# AvrispArduino.net
KiCad netlist of a schematic drawn in EAGLE
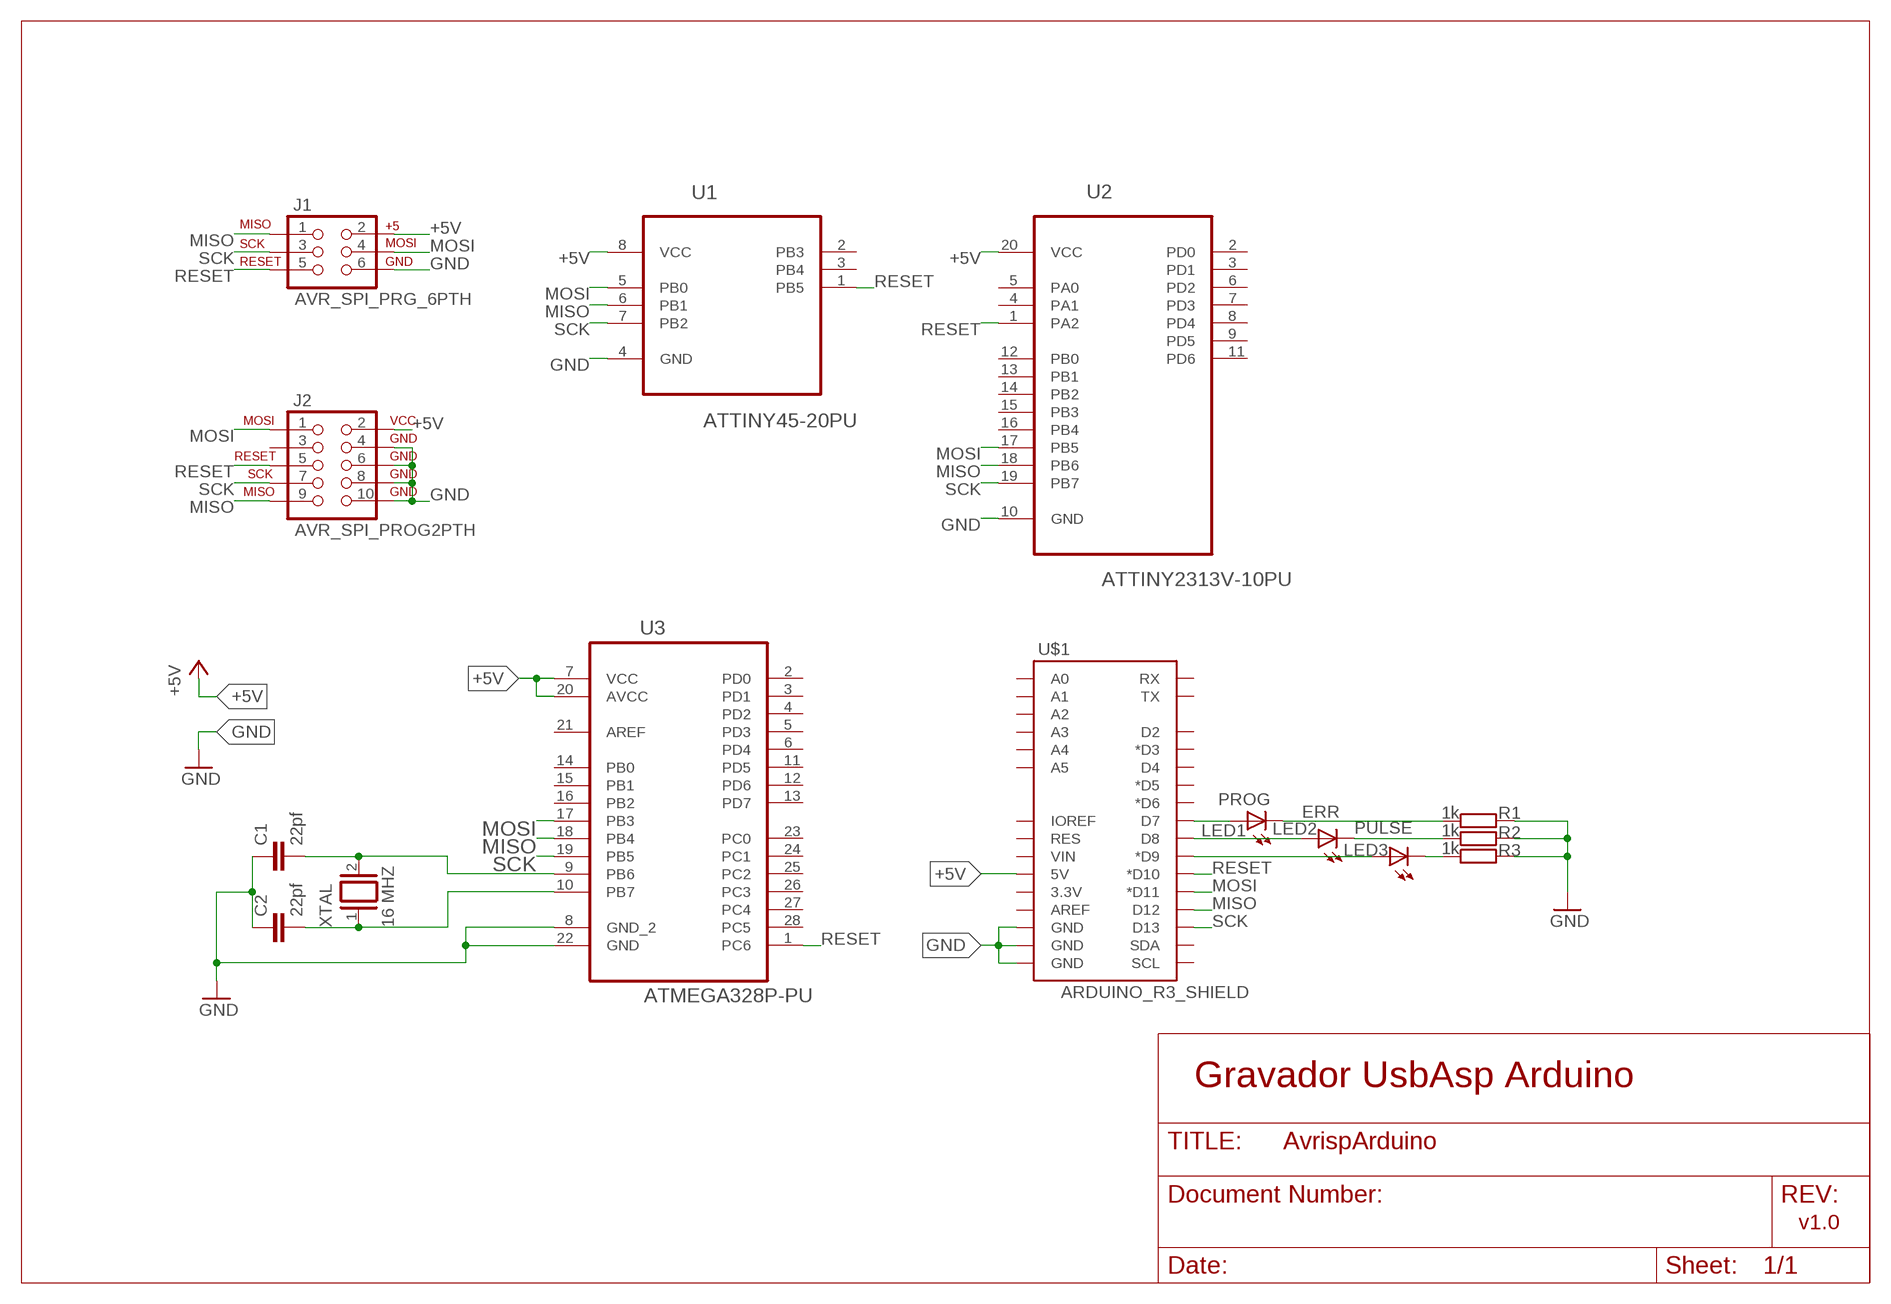
[diagram p0: schematic, sheet 1]

(export (version "E")
  (design (tool "Eeschema 10.0.6"))
  (components
    (comp (ref "C1")
      (value "22pf")
      (footprint "eagle-import:C025-025X050")
      (libsource (lib "eagle-import") (part "C-EU025-025X050"))
    )
    (comp (ref "C2")
      (value "22pf")
      (footprint "eagle-import:C025-025X050")
      (libsource (lib "eagle-import") (part "C-EU025-025X050"))
    )
    (comp (ref "J1")
      (value "AVR_SPI_PRG_6PTH")
      (footprint "eagle-import:2X3")
      (libsource (lib "eagle-import") (part "AVR_SPI_PRG_6PTH"))
    )
    (comp (ref "J2")
      (value "AVR_SPI_PROG2PTH")
      (footprint "eagle-import:AVR_ICSP")
      (libsource (lib "eagle-import") (part "AVR_SPI_PROG2PTH"))
    )
    (comp (ref "LED1")
      (value "PROG")
      (footprint "eagle-import:LED3MM")
      (libsource (lib "eagle-import") (part "LED3MM"))
    )
    (comp (ref "LED2")
      (value "ERR")
      (footprint "eagle-import:LED3MM")
      (libsource (lib "eagle-import") (part "LED3MM"))
    )
    (comp (ref "LED3")
      (value "PULSE")
      (footprint "eagle-import:LED3MM")
      (libsource (lib "eagle-import") (part "LED3MM"))
    )
    (comp (ref "R1")
      (value "1k")
      (footprint "eagle-import:0207_10")
      (libsource (lib "eagle-import") (part "R-EU_0207/10"))
    )
    (comp (ref "R2")
      (value "1k")
      (footprint "eagle-import:0207_10")
      (libsource (lib "eagle-import") (part "R-EU_0207/10"))
    )
    (comp (ref "R3")
      (value "1k")
      (footprint "eagle-import:0207_10")
      (libsource (lib "eagle-import") (part "R-EU_0207/10"))
    )
    (comp (ref "U$1")
      (value "ARDUINO_R3_SHIELD")
      (footprint "eagle-import:UNO_R3_SHIELD")
      (libsource (lib "eagle-import") (part "ARDUINO_R3_SHIELD"))
    )
    (comp (ref "U1")
      (value "ATTINY45-20PU")
      (footprint "eagle-import:DIP254P762X533-8")
      (libsource (lib "eagle-import") (part "ATTINY45-20PU"))
    )
    (comp (ref "U2")
      (value "ATTINY2313V-10PU")
      (footprint "eagle-import:DIP254P762X533-20")
      (libsource (lib "eagle-import") (part "ATTINY2313V-10PU"))
    )
    (comp (ref "U3")
      (value "ATMEGA328P-PU")
      (footprint "eagle-import:DIP254P762X457-28")
      (libsource (lib "eagle-import") (part "ATMEGA328P-PU"))
    )
    (comp (ref "XTAL")
      (value "16 MHZ")
      (footprint "eagle-import:QS")
      (libsource (lib "eagle-import") (part "XTAL/S"))
    )
  )
  (nets
    (net (code "1") (name "+5V") (class "Default")
      (node (ref "J1") (pin "2") (pinfunction "2_2") (pintype "passive"))
      (node (ref "J2") (pin "2") (pinfunction "VCC_2") (pintype "power_in"))
      (node (ref "U$1") (pin "5V") (pinfunction "5V_5V") (pintype "bidirectional"))
      (node (ref "U1") (pin "8") (pinfunction "VCC_8") (pintype "power_in"))
      (node (ref "U2") (pin "20") (pinfunction "VCC_20") (pintype "power_in"))
      (node (ref "U3") (pin "20") (pinfunction "AVCC_20") (pintype "power_in"))
      (node (ref "U3") (pin "7") (pinfunction "VCC_7") (pintype "power_in"))
    )
    (net (code "2") (name "/MISO") (class "Default")
      (node (ref "J1") (pin "1") (pinfunction "1_1") (pintype "passive"))
      (node (ref "J2") (pin "9") (pinfunction "MISO_9") (pintype "passive"))
      (node (ref "U$1") (pin "D12") (pinfunction "D12_D12") (pintype "bidirectional"))
      (node (ref "U1") (pin "6") (pinfunction "PB1_6") (pintype "bidirectional"))
      (node (ref "U2") (pin "18") (pinfunction "PB6_18") (pintype "bidirectional"))
      (node (ref "U3") (pin "18") (pinfunction "PB4_18") (pintype "bidirectional"))
    )
    (net (code "3") (name "/MOSI") (class "Default")
      (node (ref "J1") (pin "4") (pinfunction "4_4") (pintype "passive"))
      (node (ref "J2") (pin "1") (pinfunction "MOSI_1") (pintype "passive"))
      (node (ref "U$1") (pin "D11") (pinfunction "*D11_D11") (pintype "bidirectional"))
      (node (ref "U1") (pin "5") (pinfunction "PB0_5") (pintype "bidirectional"))
      (node (ref "U2") (pin "17") (pinfunction "PB5_17") (pintype "bidirectional"))
      (node (ref "U3") (pin "17") (pinfunction "PB3_17") (pintype "bidirectional"))
    )
    (net (code "4") (name "/RESET") (class "Default")
      (node (ref "J1") (pin "5") (pinfunction "5_5") (pintype "passive"))
      (node (ref "J2") (pin "5") (pinfunction "RESET_5") (pintype "passive"))
      (node (ref "U$1") (pin "D10") (pinfunction "*D10_D10") (pintype "bidirectional"))
      (node (ref "U1") (pin "1") (pinfunction "PB5_1") (pintype "bidirectional"))
      (node (ref "U2") (pin "1") (pinfunction "PA2_1") (pintype "bidirectional"))
      (node (ref "U3") (pin "1") (pinfunction "PC6_1") (pintype "bidirectional"))
    )
    (net (code "5") (name "/SCK") (class "Default")
      (node (ref "J1") (pin "3") (pinfunction "3_3") (pintype "passive"))
      (node (ref "J2") (pin "7") (pinfunction "SCK_7") (pintype "passive"))
      (node (ref "U$1") (pin "D13") (pinfunction "D13_D13") (pintype "bidirectional"))
      (node (ref "U1") (pin "7") (pinfunction "PB2_7") (pintype "bidirectional"))
      (node (ref "U2") (pin "19") (pinfunction "PB7_19") (pintype "bidirectional"))
      (node (ref "U3") (pin "19") (pinfunction "PB5_19") (pintype "bidirectional"))
    )
    (net (code "6") (name "GND") (class "Default")
      (node (ref "C1") (pin "1") (pinfunction "1_1") (pintype "passive"))
      (node (ref "C2") (pin "1") (pinfunction "1_1") (pintype "passive"))
      (node (ref "J1") (pin "6") (pinfunction "6_6") (pintype "passive"))
      (node (ref "J2") (pin "10") (pinfunction "GND_10") (pintype "power_in"))
      (node (ref "J2") (pin "4") (pinfunction "GND_4") (pintype "power_in"))
      (node (ref "J2") (pin "6") (pinfunction "GND_6") (pintype "power_in"))
      (node (ref "J2") (pin "8") (pinfunction "GND_8") (pintype "power_in"))
      (node (ref "R1") (pin "2") (pinfunction "2_2") (pintype "passive"))
      (node (ref "R2") (pin "2") (pinfunction "2_2") (pintype "passive"))
      (node (ref "R3") (pin "2") (pinfunction "2_2") (pintype "passive"))
      (node (ref "U$1") (pin "GND@0") (pinfunction "GND_GND@0") (pintype "bidirectional"))
      (node (ref "U$1") (pin "GND@1") (pinfunction "GND_GND@1") (pintype "bidirectional"))
      (node (ref "U$1") (pin "GND@2") (pinfunction "GND_GND@2") (pintype "bidirectional"))
      (node (ref "U1") (pin "4") (pinfunction "GND_4") (pintype "passive"))
      (node (ref "U2") (pin "10") (pinfunction "GND_10") (pintype "passive"))
      (node (ref "U3") (pin "22") (pinfunction "GND_22") (pintype "passive"))
      (node (ref "U3") (pin "8") (pinfunction "GND_2_8") (pintype "passive"))
    )
    (net (code "7") (name "Net-(LED1-C)") (class "Default")
      (node (ref "LED1") (pin "K") (pinfunction "C_K") (pintype "passive"))
      (node (ref "R1") (pin "1") (pinfunction "1_1") (pintype "passive"))
    )
    (net (code "8") (name "Net-(LED1-PadA)") (class "Default")
      (node (ref "LED1") (pin "A") (pinfunction "A_A") (pintype "passive"))
      (node (ref "U$1") (pin "D7") (pinfunction "D7_D7") (pintype "bidirectional"))
    )
    (net (code "9") (name "Net-(LED2-C)") (class "Default")
      (node (ref "LED2") (pin "K") (pinfunction "C_K") (pintype "passive"))
      (node (ref "R2") (pin "1") (pinfunction "1_1") (pintype "passive"))
    )
    (net (code "10") (name "Net-(LED2-PadA)") (class "Default")
      (node (ref "LED2") (pin "A") (pinfunction "A_A") (pintype "passive"))
      (node (ref "U$1") (pin "D8") (pinfunction "D8_D8") (pintype "bidirectional"))
    )
    (net (code "11") (name "Net-(LED3-C)") (class "Default")
      (node (ref "LED3") (pin "K") (pinfunction "C_K") (pintype "passive"))
      (node (ref "R3") (pin "1") (pinfunction "1_1") (pintype "passive"))
    )
    (net (code "12") (name "Net-(U$1-*D9)") (class "Default")
      (node (ref "LED3") (pin "A") (pinfunction "A_A") (pintype "passive"))
      (node (ref "U$1") (pin "D9") (pinfunction "*D9_D9") (pintype "bidirectional"))
    )
    (net (code "13") (name "Net-(U3-PB6)") (class "Default")
      (node (ref "C1") (pin "2") (pinfunction "2_2") (pintype "passive"))
      (node (ref "U3") (pin "9") (pinfunction "PB6_9") (pintype "bidirectional"))
      (node (ref "XTAL") (pin "2") (pinfunction "2_2") (pintype "passive"))
    )
    (net (code "14") (name "Net-(U3-PB7)") (class "Default")
      (node (ref "C2") (pin "2") (pinfunction "2_2") (pintype "passive"))
      (node (ref "U3") (pin "10") (pinfunction "PB7_10") (pintype "bidirectional"))
      (node (ref "XTAL") (pin "1") (pinfunction "1_1") (pintype "passive"))
    )
    (net (code "15") (name "unconnected-(J2-NC-Pad3)") (class "Default")
      (node (ref "J2") (pin "3") (pinfunction "NC_3") (pintype "no_connect"))
    )
    (net (code "16") (name "unconnected-(U$1-*D3-PadD3)") (class "Default")
      (node (ref "U$1") (pin "D3") (pinfunction "*D3_D3") (pintype "bidirectional"))
    )
    (net (code "17") (name "unconnected-(U$1-*D5-PadD5)") (class "Default")
      (node (ref "U$1") (pin "D5") (pinfunction "*D5_D5") (pintype "bidirectional"))
    )
    (net (code "18") (name "unconnected-(U$1-*D6-PadD6)") (class "Default")
      (node (ref "U$1") (pin "D6") (pinfunction "*D6_D6") (pintype "bidirectional"))
    )
    (net (code "19") (name "unconnected-(U$1-Pad3.3V)") (class "Default")
      (node (ref "U$1") (pin "3.3V") (pinfunction "3.3V_3.3V") (pintype "bidirectional"))
    )
    (net (code "20") (name "unconnected-(U$1-PadA0)") (class "Default")
      (node (ref "U$1") (pin "A0") (pinfunction "A0_A0") (pintype "bidirectional"))
    )
    (net (code "21") (name "unconnected-(U$1-PadA1)") (class "Default")
      (node (ref "U$1") (pin "A1") (pinfunction "A1_A1") (pintype "bidirectional"))
    )
    (net (code "22") (name "unconnected-(U$1-PadA2)") (class "Default")
      (node (ref "U$1") (pin "A2") (pinfunction "A2_A2") (pintype "bidirectional"))
    )
    (net (code "23") (name "unconnected-(U$1-PadA3)") (class "Default")
      (node (ref "U$1") (pin "A3") (pinfunction "A3_A3") (pintype "bidirectional"))
    )
    (net (code "24") (name "unconnected-(U$1-PadA4)") (class "Default")
      (node (ref "U$1") (pin "A4") (pinfunction "A4_A4") (pintype "bidirectional"))
    )
    (net (code "25") (name "unconnected-(U$1-PadA5)") (class "Default")
      (node (ref "U$1") (pin "A5") (pinfunction "A5_A5") (pintype "bidirectional"))
    )
    (net (code "26") (name "unconnected-(U$1-PadAREF)") (class "Default")
      (node (ref "U$1") (pin "AREF") (pinfunction "AREF_AREF") (pintype "bidirectional"))
    )
    (net (code "27") (name "unconnected-(U$1-PadD2)") (class "Default")
      (node (ref "U$1") (pin "D2") (pinfunction "D2_D2") (pintype "bidirectional"))
    )
    (net (code "28") (name "unconnected-(U$1-PadD4)") (class "Default")
      (node (ref "U$1") (pin "D4") (pinfunction "D4_D4") (pintype "bidirectional"))
    )
    (net (code "29") (name "unconnected-(U$1-PadIOREF)") (class "Default")
      (node (ref "U$1") (pin "IOREF") (pinfunction "IOREF_IOREF") (pintype "bidirectional"))
    )
    (net (code "30") (name "unconnected-(U$1-PadRES)") (class "Default")
      (node (ref "U$1") (pin "RES") (pinfunction "RES_RES") (pintype "bidirectional"))
    )
    (net (code "31") (name "unconnected-(U$1-PadRX)") (class "Default")
      (node (ref "U$1") (pin "RX") (pinfunction "RX_RX") (pintype "bidirectional"))
    )
    (net (code "32") (name "unconnected-(U$1-PadSCL)") (class "Default")
      (node (ref "U$1") (pin "SCL") (pinfunction "SCL_SCL") (pintype "bidirectional"))
    )
    (net (code "33") (name "unconnected-(U$1-PadSDA)") (class "Default")
      (node (ref "U$1") (pin "SDA") (pinfunction "SDA_SDA") (pintype "bidirectional"))
    )
    (net (code "34") (name "unconnected-(U$1-PadTX)") (class "Default")
      (node (ref "U$1") (pin "TX") (pinfunction "TX_TX") (pintype "bidirectional"))
    )
    (net (code "35") (name "unconnected-(U$1-PadVIN)") (class "Default")
      (node (ref "U$1") (pin "VIN") (pinfunction "VIN_VIN") (pintype "bidirectional"))
    )
    (net (code "36") (name "unconnected-(U1-PB3-Pad2)") (class "Default")
      (node (ref "U1") (pin "2") (pinfunction "PB3_2") (pintype "bidirectional"))
    )
    (net (code "37") (name "unconnected-(U1-PB4-Pad3)") (class "Default")
      (node (ref "U1") (pin "3") (pinfunction "PB4_3") (pintype "bidirectional"))
    )
    (net (code "38") (name "unconnected-(U2-PA0-Pad5)") (class "Default")
      (node (ref "U2") (pin "5") (pinfunction "PA0_5") (pintype "bidirectional"))
    )
    (net (code "39") (name "unconnected-(U2-PA1-Pad4)") (class "Default")
      (node (ref "U2") (pin "4") (pinfunction "PA1_4") (pintype "bidirectional"))
    )
    (net (code "40") (name "unconnected-(U2-PB0-Pad12)") (class "Default")
      (node (ref "U2") (pin "12") (pinfunction "PB0_12") (pintype "bidirectional"))
    )
    (net (code "41") (name "unconnected-(U2-PB1-Pad13)") (class "Default")
      (node (ref "U2") (pin "13") (pinfunction "PB1_13") (pintype "bidirectional"))
    )
    (net (code "42") (name "unconnected-(U2-PB2-Pad14)") (class "Default")
      (node (ref "U2") (pin "14") (pinfunction "PB2_14") (pintype "bidirectional"))
    )
    (net (code "43") (name "unconnected-(U2-PB3-Pad15)") (class "Default")
      (node (ref "U2") (pin "15") (pinfunction "PB3_15") (pintype "bidirectional"))
    )
    (net (code "44") (name "unconnected-(U2-PB4-Pad16)") (class "Default")
      (node (ref "U2") (pin "16") (pinfunction "PB4_16") (pintype "bidirectional"))
    )
    (net (code "45") (name "unconnected-(U2-PD0-Pad2)") (class "Default")
      (node (ref "U2") (pin "2") (pinfunction "PD0_2") (pintype "bidirectional"))
    )
    (net (code "46") (name "unconnected-(U2-PD1-Pad3)") (class "Default")
      (node (ref "U2") (pin "3") (pinfunction "PD1_3") (pintype "bidirectional"))
    )
    (net (code "47") (name "unconnected-(U2-PD2-Pad6)") (class "Default")
      (node (ref "U2") (pin "6") (pinfunction "PD2_6") (pintype "bidirectional"))
    )
    (net (code "48") (name "unconnected-(U2-PD3-Pad7)") (class "Default")
      (node (ref "U2") (pin "7") (pinfunction "PD3_7") (pintype "bidirectional"))
    )
    (net (code "49") (name "unconnected-(U2-PD4-Pad8)") (class "Default")
      (node (ref "U2") (pin "8") (pinfunction "PD4_8") (pintype "bidirectional"))
    )
    (net (code "50") (name "unconnected-(U2-PD5-Pad9)") (class "Default")
      (node (ref "U2") (pin "9") (pinfunction "PD5_9") (pintype "bidirectional"))
    )
    (net (code "51") (name "unconnected-(U2-PD6-Pad11)") (class "Default")
      (node (ref "U2") (pin "11") (pinfunction "PD6_11") (pintype "bidirectional"))
    )
    (net (code "52") (name "unconnected-(U3-AREF-Pad21)") (class "Default")
      (node (ref "U3") (pin "21") (pinfunction "AREF_21") (pintype "input"))
    )
    (net (code "53") (name "unconnected-(U3-PB0-Pad14)") (class "Default")
      (node (ref "U3") (pin "14") (pinfunction "PB0_14") (pintype "bidirectional"))
    )
    (net (code "54") (name "unconnected-(U3-PB1-Pad15)") (class "Default")
      (node (ref "U3") (pin "15") (pinfunction "PB1_15") (pintype "bidirectional"))
    )
    (net (code "55") (name "unconnected-(U3-PB2-Pad16)") (class "Default")
      (node (ref "U3") (pin "16") (pinfunction "PB2_16") (pintype "bidirectional"))
    )
    (net (code "56") (name "unconnected-(U3-PC0-Pad23)") (class "Default")
      (node (ref "U3") (pin "23") (pinfunction "PC0_23") (pintype "bidirectional"))
    )
    (net (code "57") (name "unconnected-(U3-PC1-Pad24)") (class "Default")
      (node (ref "U3") (pin "24") (pinfunction "PC1_24") (pintype "bidirectional"))
    )
    (net (code "58") (name "unconnected-(U3-PC2-Pad25)") (class "Default")
      (node (ref "U3") (pin "25") (pinfunction "PC2_25") (pintype "bidirectional"))
    )
    (net (code "59") (name "unconnected-(U3-PC3-Pad26)") (class "Default")
      (node (ref "U3") (pin "26") (pinfunction "PC3_26") (pintype "bidirectional"))
    )
    (net (code "60") (name "unconnected-(U3-PC4-Pad27)") (class "Default")
      (node (ref "U3") (pin "27") (pinfunction "PC4_27") (pintype "bidirectional"))
    )
    (net (code "61") (name "unconnected-(U3-PC5-Pad28)") (class "Default")
      (node (ref "U3") (pin "28") (pinfunction "PC5_28") (pintype "bidirectional"))
    )
    (net (code "62") (name "unconnected-(U3-PD0-Pad2)") (class "Default")
      (node (ref "U3") (pin "2") (pinfunction "PD0_2") (pintype "bidirectional"))
    )
    (net (code "63") (name "unconnected-(U3-PD1-Pad3)") (class "Default")
      (node (ref "U3") (pin "3") (pinfunction "PD1_3") (pintype "bidirectional"))
    )
    (net (code "64") (name "unconnected-(U3-PD2-Pad4)") (class "Default")
      (node (ref "U3") (pin "4") (pinfunction "PD2_4") (pintype "bidirectional"))
    )
    (net (code "65") (name "unconnected-(U3-PD3-Pad5)") (class "Default")
      (node (ref "U3") (pin "5") (pinfunction "PD3_5") (pintype "bidirectional"))
    )
    (net (code "66") (name "unconnected-(U3-PD4-Pad6)") (class "Default")
      (node (ref "U3") (pin "6") (pinfunction "PD4_6") (pintype "bidirectional"))
    )
    (net (code "67") (name "unconnected-(U3-PD5-Pad11)") (class "Default")
      (node (ref "U3") (pin "11") (pinfunction "PD5_11") (pintype "bidirectional"))
    )
    (net (code "68") (name "unconnected-(U3-PD6-Pad12)") (class "Default")
      (node (ref "U3") (pin "12") (pinfunction "PD6_12") (pintype "bidirectional"))
    )
    (net (code "69") (name "unconnected-(U3-PD7-Pad13)") (class "Default")
      (node (ref "U3") (pin "13") (pinfunction "PD7_13") (pintype "bidirectional"))
    )
  )
)
